# PowerModule.net
KiCad netlist of a schematic drawn in Altium Designer
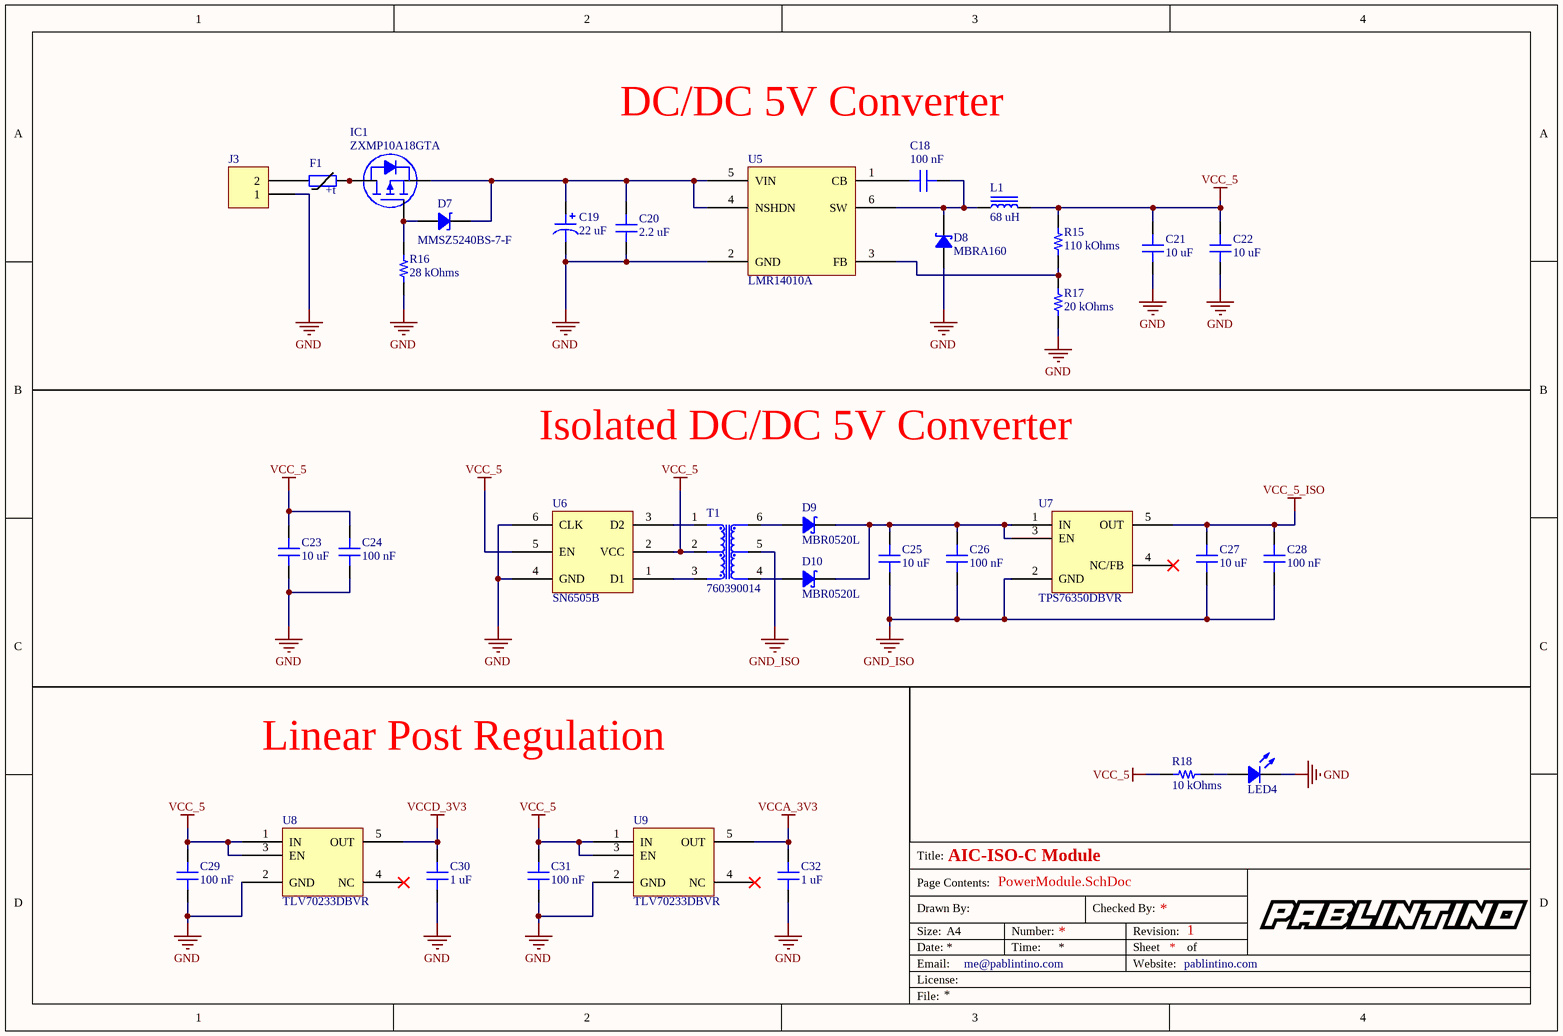
[diagram p0: PowerModule.SchDoc]

(export (version "E")
  (design (tool "Eeschema 10.0.6"))
  (components
    (comp (ref "C18")
      (value "100 nF")
      (footprint "CAP 0805_2012")
      (description "MLCC Ceramic 100 nF 50 V 10% Capacitor")
      (fields (field (name "PART NUMBER") "08055C104K4Z2A") (field (name "MANUFACTURER") "AVX"))
      (libsource (lib "Database_Libs") (part "Capacitor"))
    )
    (comp (ref "C19")
      (value "22 uF")
      (footprint "CAP ALSMD 6.3MM H7.7MM")
      (description "Aluminum Electrolytic 22 uF 63 V 20% Capacitor")
      (fields
        (field (name "PART NUMBER") "HHXA630ARA220MF80G")
        (field (name "MANUFACTURER") "United Chemi-Con")
      )
      (libsource (lib "Database_Libs") (part "Polarised Capacitor"))
    )
    (comp (ref "C20")
      (value "2.2 uF")
      (footprint "CAP 1206_3216 - 1.8MM")
      (description "MLCC Ceramic 2.2 uF 50 V 10% Capacitor")
      (fields (field (name "PART NUMBER") "12065C225K4T2A") (field (name "MANUFACTURER") "AVX"))
      (libsource (lib "Database_Libs") (part "Capacitor"))
    )
    (comp (ref "C21")
      (value "10 uF")
      (footprint "CAP 1206_3216 - 1.8MM")
      (description "MLCC Ceramic 10 uF 16 V 10% Capacitor")
      (fields (field (name "PART NUMBER") "1206YC106KAT2A") (field (name "MANUFACTURER") "AVX"))
      (libsource (lib "Database_Libs") (part "Capacitor"))
    )
    (comp (ref "C22")
      (value "10 uF")
      (footprint "CAP 1206_3216 - 1.8MM")
      (description "MLCC Ceramic 10 uF 16 V 10% Capacitor")
      (fields (field (name "PART NUMBER") "1206YC106KAT2A") (field (name "MANUFACTURER") "AVX"))
      (libsource (lib "Database_Libs") (part "Capacitor"))
    )
    (comp (ref "C23")
      (value "10 uF")
      (footprint "CAP 0805_2012")
      (description "MLCC Ceramic 10 uF 25 V 20% Capacitor")
      (fields (field (name "PART NUMBER") "0805YC106MAT2A") (field (name "MANUFACTURER") "AVX"))
      (libsource (lib "Database_Libs") (part "Capacitor"))
    )
    (comp (ref "C24")
      (value "100 nF")
      (footprint "CAP 0805_2012")
      (description "MLCC Ceramic 100 nF 16 v 10% Capacitor")
      (fields (field (name "PART NUMBER") "0805YC104KAT4A") (field (name "MANUFACTURER") "AVX"))
      (libsource (lib "Database_Libs") (part "Capacitor"))
    )
    (comp (ref "C25")
      (value "10 uF")
      (footprint "CAP 0805_2012")
      (description "MLCC Ceramic 10 uF 25 V 20% Capacitor")
      (fields (field (name "PART NUMBER") "0805YC106MAT2A") (field (name "MANUFACTURER") "AVX"))
      (libsource (lib "Database_Libs") (part "Capacitor"))
    )
    (comp (ref "C26")
      (value "100 nF")
      (footprint "CAP 0805_2012")
      (description "MLCC Ceramic 100 nF 16 v 10% Capacitor")
      (fields (field (name "PART NUMBER") "0805YC104KAT4A") (field (name "MANUFACTURER") "AVX"))
      (libsource (lib "Database_Libs") (part "Capacitor"))
    )
    (comp (ref "C27")
      (value "10 uF")
      (footprint "CAP 0805_2012")
      (description "MLCC Ceramic 10 uF 25 V 20% Capacitor")
      (fields (field (name "PART NUMBER") "0805YC106MAT2A") (field (name "MANUFACTURER") "AVX"))
      (libsource (lib "Database_Libs") (part "Capacitor"))
    )
    (comp (ref "C28")
      (value "100 nF")
      (footprint "CAP 0603_1608")
      (description "MLCC Ceramic 100 nF 16 V 10% Capacitor")
      (fields (field (name "PART NUMBER") "0603YC104KAT2A") (field (name "MANUFACTURER") "AVX"))
      (libsource (lib "Database_Libs") (part "Capacitor"))
    )
    (comp (ref "C29")
      (value "100 nF")
      (footprint "CAP 0603_1608")
      (description "MLCC Ceramic 100 nF 16 V 10% Capacitor")
      (fields (field (name "PART NUMBER") "0603YC104KAT2A") (field (name "MANUFACTURER") "AVX"))
      (libsource (lib "Database_Libs") (part "Capacitor"))
    )
    (comp (ref "C30")
      (value "1 uF")
      (footprint "CAP 0805_2012")
      (description "MLCC Ceramic 1 uF 16 V 10% Capacitor")
      (fields (field (name "PART NUMBER") "0805YC105KAT4A") (field (name "MANUFACTURER") "AVX"))
      (libsource (lib "Database_Libs") (part "Capacitor"))
    )
    (comp (ref "C31")
      (value "100 nF")
      (footprint "CAP 0603_1608")
      (description "MLCC Ceramic 100 nF 16 V 10% Capacitor")
      (fields (field (name "PART NUMBER") "0603YC104KAT2A") (field (name "MANUFACTURER") "AVX"))
      (libsource (lib "Database_Libs") (part "Capacitor"))
    )
    (comp (ref "C32")
      (value "1 uF")
      (footprint "CAP 0805_2012")
      (description "MLCC Ceramic 1 uF 16 V 10% Capacitor")
      (fields (field (name "PART NUMBER") "0805YC105KAT4A") (field (name "MANUFACTURER") "AVX"))
      (libsource (lib "Database_Libs") (part "Capacitor"))
    )
    (comp (ref "D7")
      (value "MMSZ5240BS-7-F")
      (footprint "SOD-123")
      (description "Zener 200 mW 10 V")
      (fields (field (name "MANUFACTURER") "Diodes Incorporated"))
      (libsource (lib "Database_Libs") (part "Diode Zener"))
    )
    (comp (ref "D8")
      (value "MBRA160")
      (footprint "DO214AC SMA")
      (description "Schottky Rectifier Diode")
      (fields (field (name "MANUFACTURER") "ON Semiconductor"))
      (libsource (lib "Database_Libs") (part "Schottky"))
    )
    (comp (ref "D9")
      (value "MBR0520L")
      (footprint "SOD-123")
      (description "Schottky Rectifier Diode")
      (fields (field (name "MANUFACTURER") "ON Semiconductor"))
      (libsource (lib "Database_Libs") (part "Schottky"))
    )
    (comp (ref "D10")
      (value "MBR0520L")
      (footprint "SOD-123")
      (description "Schottky Rectifier Diode")
      (fields (field (name "MANUFACTURER") "ON Semiconductor"))
      (libsource (lib "Database_Libs") (part "Schottky"))
    )
    (comp (ref "F1")
      (value "NANOASMDC012F-2")
      (footprint "PPTC_1206_1MM")
      (description "PPTC .12A 48V Nano SMD AEC-Q200")
      (fields (field (name "MANUFACTURER") "Littelfuse"))
      (libsource (lib "Database_Libs") (part "PTC FUSE"))
    )
    (comp (ref "IC1")
      (value "ZXMP10A18GTA")
      (footprint "DIODES SOT-223")
      (description "MOSFET 100V P-Chnl UMOS")
      (fields (field (name "MANUFACTURER") "Diodes Incorporated"))
      (libsource (lib "Database_Libs") (part "DIODES MOSFET P-CH SOT-223"))
    )
    (comp (ref "J3")
      (value "1757475")
      (footprint "MSTBA2")
      (description "Pluggable Terminal Blocks 2 Pos 5mm pitch Through Hole Header")
      (fields (field (name "MANUFACTURER") "Phoenix Contact") (field (name "PUBLISHER") "Altium Limited"))
      (libsource (lib "Database_Libs") (part "GEN-2-CON"))
    )
    (comp (ref "L1")
      (value "68 uH")
      (footprint "SRR1210")
      (description "Shielded SMD Power Inductor 68 uH 3 A")
      (fields (field (name "PART NUMBER") "SRR1210-680M") (field (name "MANUFACTURER") "Bourns"))
      (libsource (lib "Database_Libs") (part "Inductor"))
    )
    (comp (ref "LED4")
      (value "APTD1608LSECK")
      (footprint "LED 0603_1608 RED")
      (description "SMD Low Current Red LED")
      (fields (field (name "MANUFACTURER") "Kingbright"))
      (libsource (lib "Database_Libs") (part "LED"))
    )
    (comp (ref "R15")
      (value "110 kOhms")
      (footprint "RES 0805_2012")
      (description "Thin Film Resistor 110 kOhms 1%")
      (fields (field (name "PART NUMBER") "CRCW0805110KFKEAC") (field (name "MANUFACTURER") "Vishay / Dale"))
      (libsource (lib "Database_Libs") (part "Resistor"))
    )
    (comp (ref "R16")
      (value "28 kOhms")
      (footprint "RES 0805_2012")
      (description "Thin Film Resistor 28 kOhms 1%")
      (fields (field (name "PART NUMBER") "CRCW080528K0FKEA") (field (name "MANUFACTURER") "Vishay / Dale"))
      (libsource (lib "Database_Libs") (part "Resistor"))
    )
    (comp (ref "R17")
      (value "20 kOhms")
      (footprint "RES 0805_2012")
      (description "Thin Film Resistor 20 kOhms 1%")
      (fields (field (name "PART NUMBER") "CRCW080520K0FKEAC") (field (name "MANUFACTURER") "Vishay / Dale"))
      (libsource (lib "Database_Libs") (part "Resistor"))
    )
    (comp (ref "R18")
      (value "10 kOhms")
      (footprint "RES 0603_1608")
      (description "Thin Film Resistor 10 kOhms 1%")
      (fields (field (name "PART NUMBER") "CRCW060310K0FKEAC") (field (name "MANUFACTURER") "Vishay / Dale"))
      (libsource (lib "Database_Libs") (part "Resistor"))
    )
    (comp (ref "T1")
      (value "760390014")
      (footprint "WE7603900XX")
      (description "MID-PPTI Push-Pull Transformer for TI SN650X")
      (fields (field (name "MANUFACTURER") "Würth Elektronik"))
      (libsource (lib "Database_Libs") (part "WE_MIDDLE_TAB_PUSH_PULL_XFER"))
    )
    (comp (ref "U5")
      (value "LMR14010A")
      (footprint "TI SOT-23-6 DDC")
      (description "4-V to 40-V, 1-A Step-Down Converter With High Efficiency Eco-mode")
      (fields (field (name "MANUFACTURER") "Texas Instruments"))
      (libsource (lib "Database_Libs") (part "LMR14010A"))
    )
    (comp (ref "U6")
      (value "SN6505B")
      (footprint "TI SOT-23-6 DBV")
      (description "Low-Noise 1-A Transformer Drivers for Isolated Power Supplies")
      (fields (field (name "MANUFACTURER") "Texas Instruments"))
      (libsource (lib "Database_Libs") (part "SN6505X"))
    )
    (comp (ref "U7")
      (value "TPS76350DBVR")
      (footprint "TI SOT-23-5 DBV")
      (description "Low-Power, 150-mA, Low-Dropout Linear Regulator")
      (fields (field (name "MANUFACTURER") "Texas Instruments"))
      (libsource (lib "Database_Libs") (part "TPS763"))
    )
    (comp (ref "U8")
      (value "TLV70233DBVR")
      (footprint "TI SOT-23-5 DBV")
      (description "TLV702 300-mA, Low-IQ, Low-Dropout Regulator")
      (fields (field (name "MANUFACTURER") "Texas Instruments"))
      (libsource (lib "Database_Libs") (part "TLV702XXQDBVR"))
    )
    (comp (ref "U9")
      (value "TLV70233DBVR")
      (footprint "TI SOT-23-5 DBV")
      (description "TLV702 300-mA, Low-IQ, Low-Dropout Regulator")
      (fields (field (name "MANUFACTURER") "Texas Instruments"))
      (libsource (lib "Database_Libs") (part "TLV702XXQDBVR"))
    )
  )
  (nets
    (net (code "1") (name "GND") (class "Default")
      (node (ref "C19") (pin "2") (pinfunction "2_2") (pintype "passive"))
      (node (ref "C20") (pin "2") (pinfunction "2_2") (pintype "passive"))
      (node (ref "C21") (pin "2") (pinfunction "2_2") (pintype "passive"))
      (node (ref "C22") (pin "2") (pinfunction "2_2") (pintype "passive"))
      (node (ref "C23") (pin "2") (pinfunction "2_2") (pintype "passive"))
      (node (ref "C24") (pin "2") (pinfunction "2_2") (pintype "passive"))
      (node (ref "C29") (pin "2") (pinfunction "2_2") (pintype "passive"))
      (node (ref "C30") (pin "2") (pinfunction "2_2") (pintype "passive"))
      (node (ref "C31") (pin "2") (pinfunction "2_2") (pintype "passive"))
      (node (ref "C32") (pin "2") (pinfunction "2_2") (pintype "passive"))
      (node (ref "D8") (pin "1") (pinfunction "1_1") (pintype "passive"))
      (node (ref "J3") (pin "1") (pinfunction "1_1") (pintype "passive"))
      (node (ref "LED4") (pin "2") (pinfunction "2_2") (pintype "passive"))
      (node (ref "R16") (pin "1") (pinfunction "1_1") (pintype "passive"))
      (node (ref "R17") (pin "2") (pinfunction "2_2") (pintype "passive"))
      (node (ref "U5") (pin "2") (pinfunction "GND_2") (pintype "passive"))
      (node (ref "U6") (pin "4") (pinfunction "GND_4") (pintype "passive"))
      (node (ref "U6") (pin "6") (pinfunction "CLK_6") (pintype "passive"))
      (node (ref "U8") (pin "2") (pinfunction "GND_2") (pintype "passive"))
      (node (ref "U9") (pin "2") (pinfunction "GND_2") (pintype "passive"))
    )
    (net (code "2") (name "GND_ISO") (class "Default")
      (node (ref "C25") (pin "2") (pinfunction "2_2") (pintype "passive"))
      (node (ref "C26") (pin "2") (pinfunction "2_2") (pintype "passive"))
      (node (ref "C27") (pin "2") (pinfunction "2_2") (pintype "passive"))
      (node (ref "C28") (pin "2") (pinfunction "2_2") (pintype "passive"))
      (node (ref "T1") (pin "5") (pinfunction "5_5") (pintype "passive"))
      (node (ref "U7") (pin "2") (pinfunction "GND_2") (pintype "passive"))
    )
    (net (code "3") (name "Net-(D9-Pad1)") (class "Default")
      (node (ref "D9") (pin "1") (pinfunction "1_1") (pintype "passive"))
      (node (ref "T1") (pin "6") (pinfunction "6_6") (pintype "passive"))
    )
    (net (code "4") (name "Net-(D10-Pad1)") (class "Default")
      (node (ref "D10") (pin "1") (pinfunction "1_1") (pintype "passive"))
      (node (ref "T1") (pin "4") (pinfunction "4_4") (pintype "passive"))
    )
    (net (code "5") (name "Net-(F1-Pad1)") (class "Default")
      (node (ref "F1") (pin "1") (pintype "passive"))
      (node (ref "J3") (pin "2") (pinfunction "2_2") (pintype "passive"))
    )
    (net (code "6") (name "Net-(F1-Pad2)") (class "Default")
      (node (ref "F1") (pin "2") (pintype "passive"))
      (node (ref "IC1") (pin "2") (pinfunction "D_2") (pintype "passive"))
      (node (ref "IC1") (pin "4") (pinfunction "D_4") (pintype "passive"))
    )
    (net (code "7") (name "Net-(IC1-G)") (class "Default")
      (node (ref "D7") (pin "1") (pinfunction "1_1") (pintype "passive"))
      (node (ref "IC1") (pin "1") (pinfunction "G_1") (pintype "passive"))
      (node (ref "R16") (pin "2") (pinfunction "2_2") (pintype "passive"))
    )
    (net (code "8") (name "Net-(IC1-S)") (class "Default")
      (node (ref "C19") (pin "1") (pinfunction "1_1") (pintype "passive"))
      (node (ref "C20") (pin "1") (pinfunction "1_1") (pintype "passive"))
      (node (ref "D7") (pin "2") (pinfunction "2_2") (pintype "passive"))
      (node (ref "IC1") (pin "3") (pinfunction "S_3") (pintype "passive"))
      (node (ref "U5") (pin "4") (pinfunction "NSHDN_4") (pintype "passive"))
      (node (ref "U5") (pin "5") (pinfunction "VIN_5") (pintype "passive"))
    )
    (net (code "9") (name "Net-(LED4-Pad1)") (class "Default")
      (node (ref "LED4") (pin "1") (pinfunction "1_1") (pintype "passive"))
      (node (ref "R18") (pin "2") (pinfunction "2_2") (pintype "passive"))
    )
    (net (code "10") (name "Net-(U5-CB)") (class "Default")
      (node (ref "C18") (pin "2") (pinfunction "2_2") (pintype "passive"))
      (node (ref "U5") (pin "1") (pinfunction "CB_1") (pintype "passive"))
    )
    (net (code "11") (name "Net-(U5-FB)") (class "Default")
      (node (ref "R15") (pin "2") (pinfunction "2_2") (pintype "passive"))
      (node (ref "R17") (pin "1") (pinfunction "1_1") (pintype "passive"))
      (node (ref "U5") (pin "3") (pinfunction "FB_3") (pintype "passive"))
    )
    (net (code "12") (name "Net-(U5-SW)") (class "Default")
      (node (ref "C18") (pin "1") (pinfunction "1_1") (pintype "passive"))
      (node (ref "D8") (pin "2") (pinfunction "2_2") (pintype "passive"))
      (node (ref "L1") (pin "1") (pinfunction "1_1") (pintype "passive"))
      (node (ref "U5") (pin "6") (pinfunction "SW_6") (pintype "passive"))
    )
    (net (code "13") (name "Net-(U6-D1)") (class "Default")
      (node (ref "T1") (pin "3") (pinfunction "3_3") (pintype "passive"))
      (node (ref "U6") (pin "1") (pinfunction "D1_1") (pintype "passive"))
    )
    (net (code "14") (name "Net-(U6-D2)") (class "Default")
      (node (ref "T1") (pin "1") (pinfunction "1_1") (pintype "passive"))
      (node (ref "U6") (pin "3") (pinfunction "D2_3") (pintype "passive"))
    )
    (net (code "15") (name "Net-(U7-EN)") (class "Default")
      (node (ref "C25") (pin "1") (pinfunction "1_1") (pintype "passive"))
      (node (ref "C26") (pin "1") (pinfunction "1_1") (pintype "passive"))
      (node (ref "D10") (pin "2") (pinfunction "2_2") (pintype "passive"))
      (node (ref "D9") (pin "2") (pinfunction "2_2") (pintype "passive"))
      (node (ref "U7") (pin "1") (pinfunction "IN_1") (pintype "passive"))
      (node (ref "U7") (pin "3") (pinfunction "EN_3") (pintype "passive"))
    )
    (net (code "16") (name "VCCA_3V3") (class "Default")
      (node (ref "C32") (pin "1") (pinfunction "1_1") (pintype "passive"))
      (node (ref "U9") (pin "5") (pinfunction "OUT_5") (pintype "passive"))
    )
    (net (code "17") (name "VCCD_3V3") (class "Default")
      (node (ref "C30") (pin "1") (pinfunction "1_1") (pintype "passive"))
      (node (ref "U8") (pin "5") (pinfunction "OUT_5") (pintype "passive"))
    )
    (net (code "18") (name "VCC_5") (class "Default")
      (node (ref "C21") (pin "1") (pinfunction "1_1") (pintype "passive"))
      (node (ref "C22") (pin "1") (pinfunction "1_1") (pintype "passive"))
      (node (ref "C23") (pin "1") (pinfunction "1_1") (pintype "passive"))
      (node (ref "C24") (pin "1") (pinfunction "1_1") (pintype "passive"))
      (node (ref "C29") (pin "1") (pinfunction "1_1") (pintype "passive"))
      (node (ref "C31") (pin "1") (pinfunction "1_1") (pintype "passive"))
      (node (ref "L1") (pin "2") (pinfunction "2_2") (pintype "passive"))
      (node (ref "R15") (pin "1") (pinfunction "1_1") (pintype "passive"))
      (node (ref "R18") (pin "1") (pinfunction "1_1") (pintype "passive"))
      (node (ref "T1") (pin "2") (pinfunction "2_2") (pintype "passive"))
      (node (ref "U6") (pin "2") (pinfunction "VCC_2") (pintype "passive"))
      (node (ref "U6") (pin "5") (pinfunction "EN_5") (pintype "passive"))
      (node (ref "U8") (pin "1") (pinfunction "IN_1") (pintype "passive"))
      (node (ref "U8") (pin "3") (pinfunction "EN_3") (pintype "passive"))
      (node (ref "U9") (pin "1") (pinfunction "IN_1") (pintype "passive"))
      (node (ref "U9") (pin "3") (pinfunction "EN_3") (pintype "passive"))
    )
    (net (code "19") (name "VCC_5_ISO") (class "Default")
      (node (ref "C27") (pin "1") (pinfunction "1_1") (pintype "passive"))
      (node (ref "C28") (pin "1") (pinfunction "1_1") (pintype "passive"))
      (node (ref "U7") (pin "5") (pinfunction "OUT_5") (pintype "passive"))
    )
    (net (code "20") (name "unconnected-(U7-NC{slash}FB-Pad4)") (class "Default")
      (node (ref "U7") (pin "4") (pinfunction "NC/FB_4") (pintype "passive+no_connect"))
    )
    (net (code "21") (name "unconnected-(U8-NC-Pad4)") (class "Default")
      (node (ref "U8") (pin "4") (pinfunction "NC_4") (pintype "passive+no_connect"))
    )
    (net (code "22") (name "unconnected-(U9-NC-Pad4)") (class "Default")
      (node (ref "U9") (pin "4") (pinfunction "NC_4") (pintype "passive+no_connect"))
    )
  )
)
